# lens_controller2.net
KiCad netlist of a schematic drawn in EAGLE
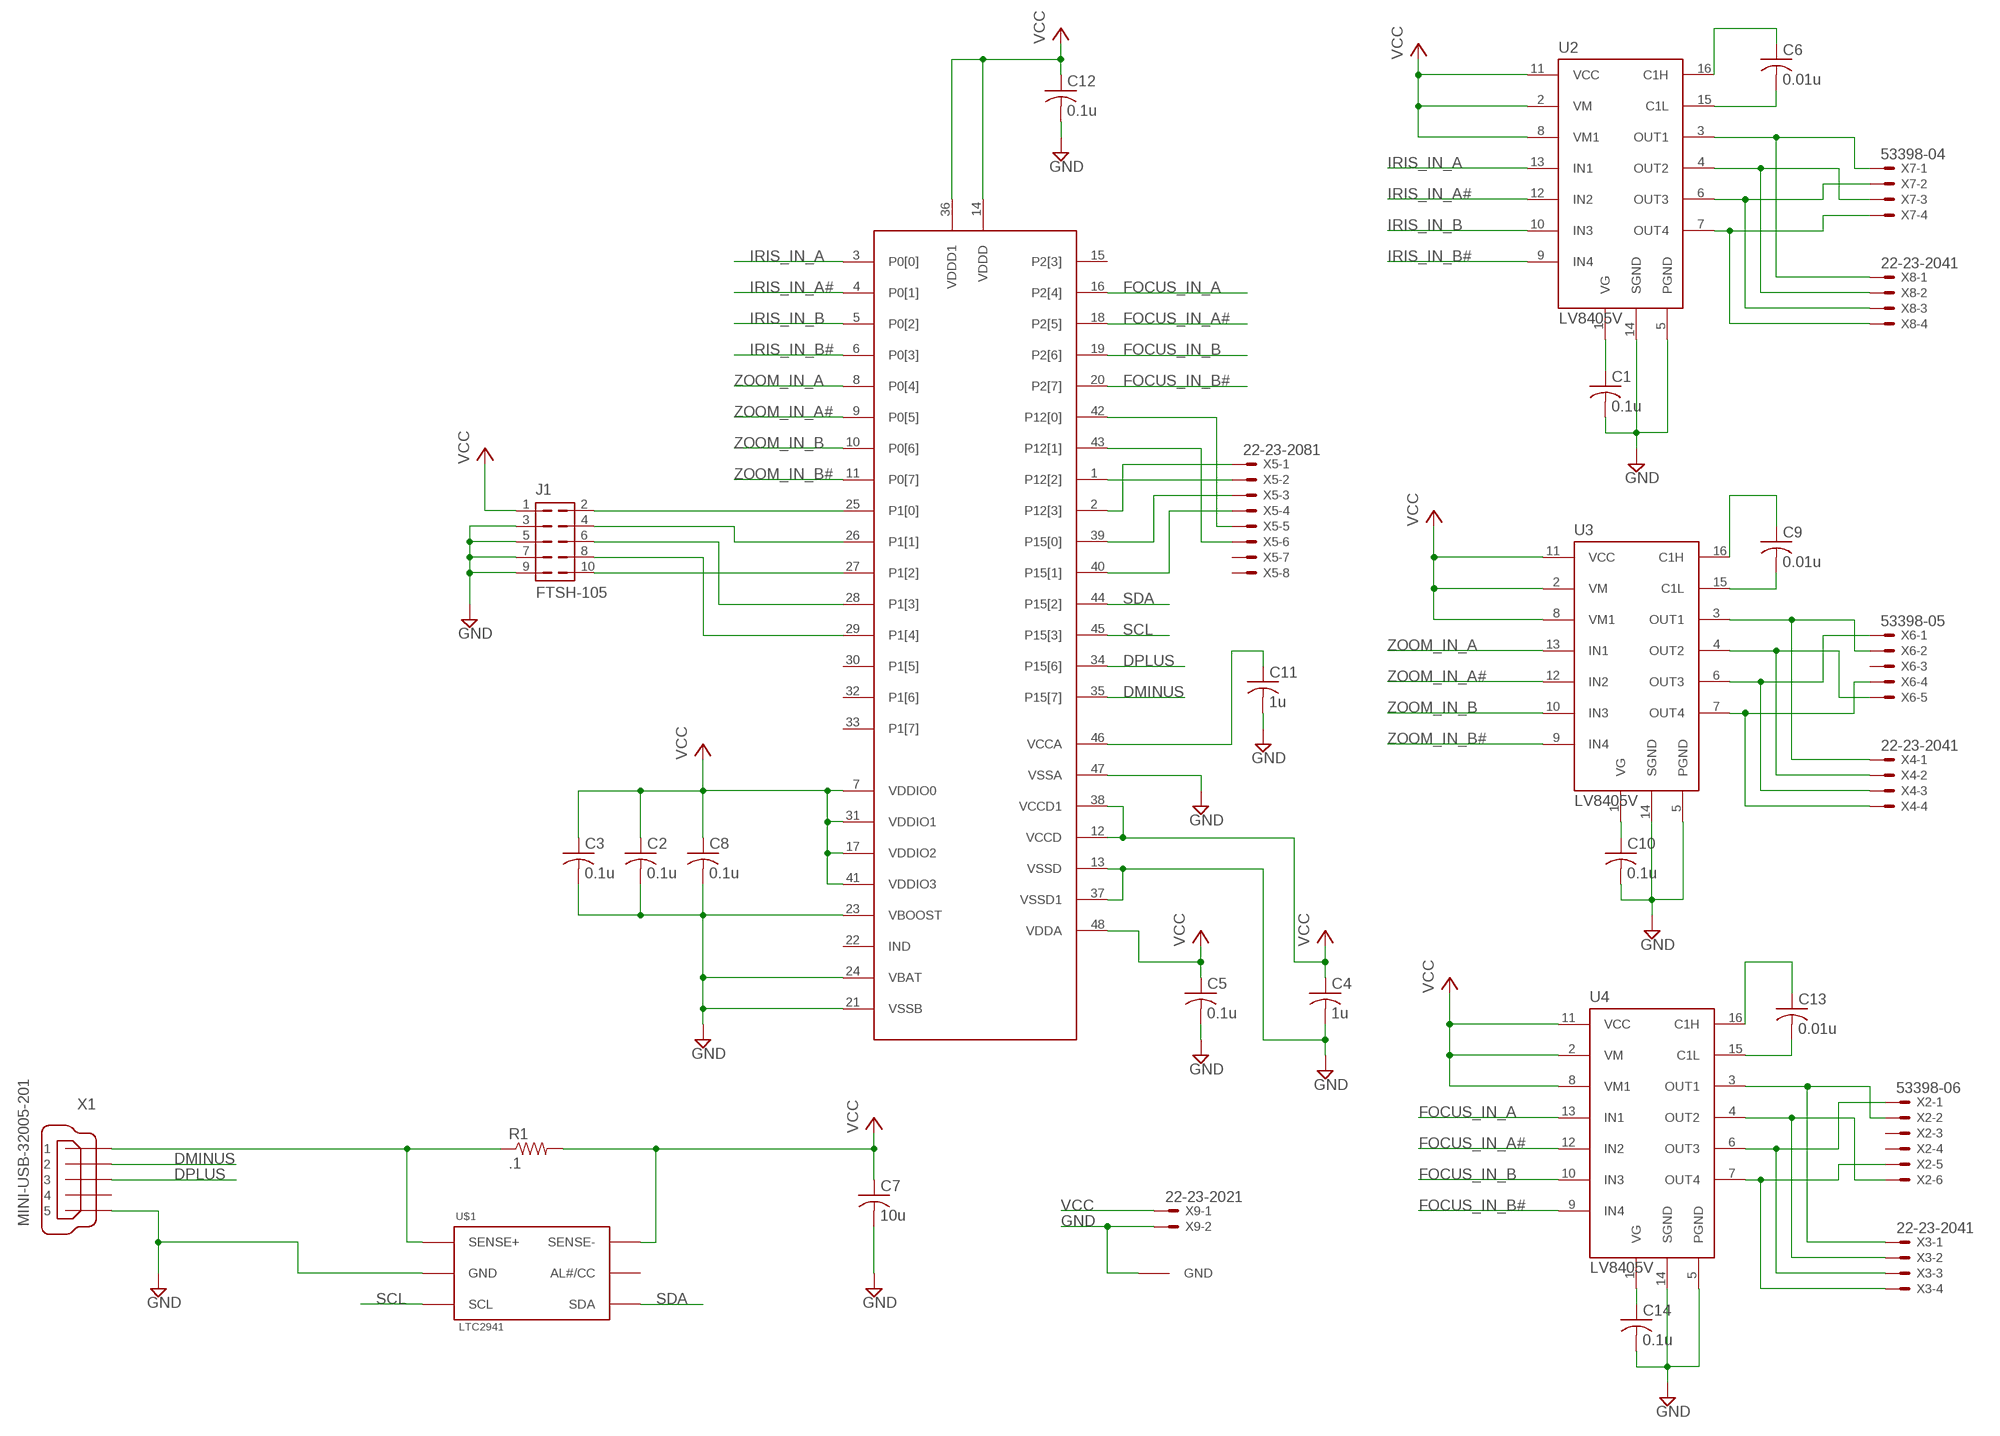
[diagram p0: schematic, sheet 1]

(export (version "E")
  (design (tool "Eeschema 10.0.6"))
  (components
    (comp (ref "C1")
      (value "0.1u")
      (footprint "eagle-import:C1206")
      (libsource (lib "eagle-import") (part "C-USC1206"))
    )
    (comp (ref "C2")
      (value "0.1u")
      (footprint "eagle-import:C1206")
      (libsource (lib "eagle-import") (part "C-USC1206"))
    )
    (comp (ref "C3")
      (value "0.1u")
      (footprint "eagle-import:C1206")
      (libsource (lib "eagle-import") (part "C-USC1206"))
    )
    (comp (ref "C4")
      (value "1u")
      (footprint "eagle-import:C1206")
      (libsource (lib "eagle-import") (part "C-USC1206"))
    )
    (comp (ref "C5")
      (value "0.1u")
      (footprint "eagle-import:C1206")
      (libsource (lib "eagle-import") (part "C-USC1206"))
    )
    (comp (ref "C6")
      (value "0.01u")
      (footprint "eagle-import:C1206")
      (libsource (lib "eagle-import") (part "C-USC1206"))
    )
    (comp (ref "C7")
      (value "10u")
      (footprint "eagle-import:C1206")
      (libsource (lib "eagle-import") (part "C-USC1206"))
    )
    (comp (ref "C8")
      (value "0.1u")
      (footprint "eagle-import:C1206")
      (libsource (lib "eagle-import") (part "C-USC1206"))
    )
    (comp (ref "C9")
      (value "0.01u")
      (footprint "eagle-import:C1206")
      (libsource (lib "eagle-import") (part "C-USC1206"))
    )
    (comp (ref "C10")
      (value "0.1u")
      (footprint "eagle-import:C1206")
      (libsource (lib "eagle-import") (part "C-USC1206"))
    )
    (comp (ref "C11")
      (value "1u")
      (footprint "eagle-import:C1206")
      (libsource (lib "eagle-import") (part "C-USC1206"))
    )
    (comp (ref "C12")
      (value "0.1u")
      (footprint "eagle-import:C1206")
      (libsource (lib "eagle-import") (part "C-USC1206"))
    )
    (comp (ref "C13")
      (value "0.01u")
      (footprint "eagle-import:C1206")
      (libsource (lib "eagle-import") (part "C-USC1206"))
    )
    (comp (ref "C14")
      (value "0.1u")
      (footprint "eagle-import:C1206")
      (libsource (lib "eagle-import") (part "C-USC1206"))
    )
    (comp (ref "J1")
      (value "FTSH-105")
      (footprint "eagle-import:FTSH-105-01-XXX-DV-K")
      (libsource (lib "eagle-import") (part "FTSH-105"))
    )
    (comp (ref "R1")
      (value ".1")
      (footprint "eagle-import:M1206")
      (libsource (lib "eagle-import") (part "R-US_M1206"))
    )
    (comp (ref "U$1")
      (value "LTC2941")
      (footprint "eagle-import:DFN6-2X3")
      (libsource (lib "eagle-import") (part "LTC2941"))
    )
    (comp (ref "U$5")
      (value "GND_LUG")
      (footprint "eagle-import:GND_PAD")
      (libsource (lib "eagle-import") (part "GND_LUG"))
    )
    (comp (ref "U1")
      (value "CY8C3246PVI")
      (footprint "eagle-import:SSOP48B")
      (libsource (lib "eagle-import") (part "CY8C3246PVI"))
    )
    (comp (ref "U2")
      (value "LV8405V")
      (footprint "eagle-import:SSOP16")
      (libsource (lib "eagle-import") (part "LV8405V"))
    )
    (comp (ref "U3")
      (value "LV8405V")
      (footprint "eagle-import:SSOP16")
      (libsource (lib "eagle-import") (part "LV8405V"))
    )
    (comp (ref "U4")
      (value "LV8405V")
      (footprint "eagle-import:SSOP16")
      (libsource (lib "eagle-import") (part "LV8405V"))
    )
    (comp (ref "X1")
      (value "MINI-USB-32005-201")
      (footprint "eagle-import:32005-201")
      (libsource (lib "eagle-import") (part "MINI-USB-32005-201"))
    )
    (comp (ref "X2")
      (value "53398-06")
      (footprint "eagle-import:53398-06")
      (libsource (lib "eagle-import") (part "53?-06398"))
    )
    (comp (ref "X3")
      (value "22-23-2041")
      (footprint "eagle-import:22-23-2041")
      (fields (field (name "MF") "MOLEX"))
      (libsource (lib "eagle-import") (part "22-23-2041"))
    )
    (comp (ref "X4")
      (value "22-23-2041")
      (footprint "eagle-import:22-23-2041")
      (fields (field (name "MF") "MOLEX"))
      (libsource (lib "eagle-import") (part "22-23-2041"))
    )
    (comp (ref "X5")
      (value "22-23-2081")
      (footprint "eagle-import:22-23-2081")
      (fields (field (name "MF") "MOLEX"))
      (libsource (lib "eagle-import") (part "22-23-2081"))
    )
    (comp (ref "X6")
      (value "53398-05")
      (footprint "eagle-import:53398-05")
      (libsource (lib "eagle-import") (part "53?-05398"))
    )
    (comp (ref "X7")
      (value "53398-04")
      (footprint "eagle-import:53398-04")
      (libsource (lib "eagle-import") (part "53?-04398"))
    )
    (comp (ref "X8")
      (value "22-23-2041")
      (footprint "eagle-import:22-23-2041")
      (fields (field (name "MF") "MOLEX"))
      (libsource (lib "eagle-import") (part "22-23-2041"))
    )
    (comp (ref "X9")
      (value "22-23-2021")
      (footprint "eagle-import:22-23-2021")
      (fields (field (name "MF") "MOLEX"))
      (libsource (lib "eagle-import") (part "22-23-2021"))
    )
  )
  (nets
    (net (code "1") (name "/DMINUS") (class "Default")
      (node (ref "U1") (pin "35") (pinfunction "P15[7]_35") (pintype "bidirectional"))
      (node (ref "X1") (pin "2") (pinfunction "2_2") (pintype "passive"))
    )
    (net (code "2") (name "/DPLUS") (class "Default")
      (node (ref "U1") (pin "34") (pinfunction "P15[6]_34") (pintype "bidirectional"))
      (node (ref "X1") (pin "3") (pinfunction "3_3") (pintype "passive"))
    )
    (net (code "3") (name "/FOCUS_IN_A") (class "Default")
      (node (ref "U1") (pin "16") (pinfunction "P2[4]_16") (pintype "bidirectional"))
      (node (ref "U4") (pin "13") (pinfunction "IN1_13") (pintype "bidirectional"))
    )
    (net (code "4") (name "/FOCUS_IN_A#") (class "Default")
      (node (ref "U1") (pin "18") (pinfunction "P2[5]_18") (pintype "bidirectional"))
      (node (ref "U4") (pin "12") (pinfunction "IN2_12") (pintype "bidirectional"))
    )
    (net (code "5") (name "/FOCUS_IN_B") (class "Default")
      (node (ref "U1") (pin "19") (pinfunction "P2[6]_19") (pintype "bidirectional"))
      (node (ref "U4") (pin "10") (pinfunction "IN3_10") (pintype "bidirectional"))
    )
    (net (code "6") (name "/FOCUS_IN_B#") (class "Default")
      (node (ref "U1") (pin "20") (pinfunction "P2[7]_20") (pintype "bidirectional"))
      (node (ref "U4") (pin "9") (pinfunction "IN4_9") (pintype "bidirectional"))
    )
    (net (code "7") (name "/IRIS_IN_A") (class "Default")
      (node (ref "U1") (pin "3") (pinfunction "P0[0]_3") (pintype "bidirectional"))
      (node (ref "U2") (pin "13") (pinfunction "IN1_13") (pintype "bidirectional"))
    )
    (net (code "8") (name "/IRIS_IN_A#") (class "Default")
      (node (ref "U1") (pin "4") (pinfunction "P0[1]_4") (pintype "bidirectional"))
      (node (ref "U2") (pin "12") (pinfunction "IN2_12") (pintype "bidirectional"))
    )
    (net (code "9") (name "/IRIS_IN_B") (class "Default")
      (node (ref "U1") (pin "5") (pinfunction "P0[2]_5") (pintype "bidirectional"))
      (node (ref "U2") (pin "10") (pinfunction "IN3_10") (pintype "bidirectional"))
    )
    (net (code "10") (name "/IRIS_IN_B#") (class "Default")
      (node (ref "U1") (pin "6") (pinfunction "P0[3]_6") (pintype "bidirectional"))
      (node (ref "U2") (pin "9") (pinfunction "IN4_9") (pintype "bidirectional"))
    )
    (net (code "11") (name "/SCL") (class "Default")
      (node (ref "U$1") (pin "3") (pinfunction "SCL_3") (pintype "bidirectional"))
      (node (ref "U1") (pin "45") (pinfunction "P15[3]_45") (pintype "bidirectional"))
    )
    (net (code "12") (name "/SDA") (class "Default")
      (node (ref "U$1") (pin "4") (pinfunction "SDA_4") (pintype "bidirectional"))
      (node (ref "U1") (pin "44") (pinfunction "P15[2]_44") (pintype "bidirectional"))
    )
    (net (code "13") (name "/ZOOM_IN_A") (class "Default")
      (node (ref "U1") (pin "8") (pinfunction "P0[4]_8") (pintype "bidirectional"))
      (node (ref "U3") (pin "13") (pinfunction "IN1_13") (pintype "bidirectional"))
    )
    (net (code "14") (name "/ZOOM_IN_A#") (class "Default")
      (node (ref "U1") (pin "9") (pinfunction "P0[5]_9") (pintype "bidirectional"))
      (node (ref "U3") (pin "12") (pinfunction "IN2_12") (pintype "bidirectional"))
    )
    (net (code "15") (name "/ZOOM_IN_B") (class "Default")
      (node (ref "U1") (pin "10") (pinfunction "P0[6]_10") (pintype "bidirectional"))
      (node (ref "U3") (pin "10") (pinfunction "IN3_10") (pintype "bidirectional"))
    )
    (net (code "16") (name "/ZOOM_IN_B#") (class "Default")
      (node (ref "U1") (pin "11") (pinfunction "P0[7]_11") (pintype "bidirectional"))
      (node (ref "U3") (pin "9") (pinfunction "IN4_9") (pintype "bidirectional"))
    )
    (net (code "17") (name "GND") (class "Default")
      (node (ref "C1") (pin "2") (pinfunction "2_2") (pintype "passive"))
      (node (ref "C10") (pin "2") (pinfunction "2_2") (pintype "passive"))
      (node (ref "C11") (pin "2") (pinfunction "2_2") (pintype "passive"))
      (node (ref "C12") (pin "2") (pinfunction "2_2") (pintype "passive"))
      (node (ref "C14") (pin "2") (pinfunction "2_2") (pintype "passive"))
      (node (ref "C2") (pin "2") (pinfunction "2_2") (pintype "passive"))
      (node (ref "C3") (pin "2") (pinfunction "2_2") (pintype "passive"))
      (node (ref "C4") (pin "2") (pinfunction "2_2") (pintype "passive"))
      (node (ref "C5") (pin "2") (pinfunction "2_2") (pintype "passive"))
      (node (ref "C7") (pin "2") (pinfunction "2_2") (pintype "passive"))
      (node (ref "C8") (pin "2") (pinfunction "2_2") (pintype "passive"))
      (node (ref "J1") (pin "3") (pinfunction "3_3") (pintype "passive"))
      (node (ref "J1") (pin "5") (pinfunction "5_5") (pintype "passive"))
      (node (ref "J1") (pin "7") (pinfunction "7_7") (pintype "passive"))
      (node (ref "J1") (pin "9") (pinfunction "9_9") (pintype "passive"))
      (node (ref "U$1") (pin "2") (pinfunction "GND_2") (pintype "bidirectional"))
      (node (ref "U$5") (pin "P$1") (pinfunction "GND_P$1") (pintype "bidirectional"))
      (node (ref "U1") (pin "13") (pinfunction "VSSD_13") (pintype "bidirectional"))
      (node (ref "U1") (pin "21") (pinfunction "VSSB_21") (pintype "bidirectional"))
      (node (ref "U1") (pin "23") (pinfunction "VBOOST_23") (pintype "bidirectional"))
      (node (ref "U1") (pin "24") (pinfunction "VBAT_24") (pintype "bidirectional"))
      (node (ref "U1") (pin "37") (pinfunction "VSSD1_37") (pintype "bidirectional"))
      (node (ref "U1") (pin "47") (pinfunction "VSSA_47") (pintype "bidirectional"))
      (node (ref "U2") (pin "14") (pinfunction "SGND_14") (pintype "bidirectional"))
      (node (ref "U2") (pin "5") (pinfunction "PGND_5") (pintype "bidirectional"))
      (node (ref "U3") (pin "14") (pinfunction "SGND_14") (pintype "bidirectional"))
      (node (ref "U3") (pin "5") (pinfunction "PGND_5") (pintype "bidirectional"))
      (node (ref "U4") (pin "14") (pinfunction "SGND_14") (pintype "bidirectional"))
      (node (ref "U4") (pin "5") (pinfunction "PGND_5") (pintype "bidirectional"))
      (node (ref "X1") (pin "5") (pinfunction "5_5") (pintype "passive"))
      (node (ref "X9") (pin "2") (pinfunction "S_2") (pintype "passive"))
    )
    (net (code "18") (name "Net-(U$1-SENSE+)") (class "Default")
      (node (ref "R1") (pin "1") (pinfunction "1_1") (pintype "passive"))
      (node (ref "U$1") (pin "1") (pinfunction "SENSE+_1") (pintype "bidirectional"))
      (node (ref "X1") (pin "1") (pinfunction "1_1") (pintype "passive"))
    )
    (net (code "19") (name "Net-(U1-P1[0])") (class "Default")
      (node (ref "J1") (pin "2") (pinfunction "2_2") (pintype "passive"))
      (node (ref "U1") (pin "25") (pinfunction "P1[0]_25") (pintype "bidirectional"))
    )
    (net (code "20") (name "Net-(U1-P1[1])") (class "Default")
      (node (ref "J1") (pin "4") (pinfunction "4_4") (pintype "passive"))
      (node (ref "U1") (pin "26") (pinfunction "P1[1]_26") (pintype "bidirectional"))
    )
    (net (code "21") (name "Net-(U1-P1[2])") (class "Default")
      (node (ref "J1") (pin "10") (pinfunction "10_10") (pintype "passive"))
      (node (ref "U1") (pin "27") (pinfunction "P1[2]_27") (pintype "bidirectional"))
    )
    (net (code "22") (name "Net-(U1-P1[3])") (class "Default")
      (node (ref "J1") (pin "6") (pinfunction "6_6") (pintype "passive"))
      (node (ref "U1") (pin "28") (pinfunction "P1[3]_28") (pintype "bidirectional"))
    )
    (net (code "23") (name "Net-(U1-P1[4])") (class "Default")
      (node (ref "J1") (pin "8") (pinfunction "8_8") (pintype "passive"))
      (node (ref "U1") (pin "29") (pinfunction "P1[4]_29") (pintype "bidirectional"))
    )
    (net (code "24") (name "Net-(U1-P12[0])") (class "Default")
      (node (ref "U1") (pin "42") (pinfunction "P12[0]_42") (pintype "bidirectional"))
      (node (ref "X5") (pin "5") (pinfunction "S_5") (pintype "passive"))
    )
    (net (code "25") (name "Net-(U1-P12[1])") (class "Default")
      (node (ref "U1") (pin "43") (pinfunction "P12[1]_43") (pintype "bidirectional"))
      (node (ref "X5") (pin "6") (pinfunction "S_6") (pintype "passive"))
    )
    (net (code "26") (name "Net-(U1-P12[2])") (class "Default")
      (node (ref "U1") (pin "1") (pinfunction "P12[2]_1") (pintype "bidirectional"))
      (node (ref "X5") (pin "2") (pinfunction "S_2") (pintype "passive"))
    )
    (net (code "27") (name "Net-(U1-P12[3])") (class "Default")
      (node (ref "U1") (pin "2") (pinfunction "P12[3]_2") (pintype "bidirectional"))
      (node (ref "X5") (pin "1") (pinfunction "S_1") (pintype "passive"))
    )
    (net (code "28") (name "Net-(U1-P15[0])") (class "Default")
      (node (ref "U1") (pin "39") (pinfunction "P15[0]_39") (pintype "bidirectional"))
      (node (ref "X5") (pin "3") (pinfunction "S_3") (pintype "passive"))
    )
    (net (code "29") (name "Net-(U1-P15[1])") (class "Default")
      (node (ref "U1") (pin "40") (pinfunction "P15[1]_40") (pintype "bidirectional"))
      (node (ref "X5") (pin "4") (pinfunction "S_4") (pintype "passive"))
    )
    (net (code "30") (name "Net-(U1-VCCA)") (class "Default")
      (node (ref "C11") (pin "1") (pinfunction "1_1") (pintype "passive"))
      (node (ref "U1") (pin "46") (pinfunction "VCCA_46") (pintype "bidirectional"))
    )
    (net (code "31") (name "Net-(U2-C1H)") (class "Default")
      (node (ref "C6") (pin "1") (pinfunction "1_1") (pintype "passive"))
      (node (ref "U2") (pin "16") (pinfunction "C1H_16") (pintype "bidirectional"))
    )
    (net (code "32") (name "Net-(U2-C1L)") (class "Default")
      (node (ref "C6") (pin "2") (pinfunction "2_2") (pintype "passive"))
      (node (ref "U2") (pin "15") (pinfunction "C1L_15") (pintype "bidirectional"))
    )
    (net (code "33") (name "Net-(U2-OUT1)") (class "Default")
      (node (ref "U2") (pin "3") (pinfunction "OUT1_3") (pintype "bidirectional"))
      (node (ref "X7") (pin "1") (pinfunction "S_1") (pintype "passive"))
      (node (ref "X8") (pin "1") (pinfunction "S_1") (pintype "passive"))
    )
    (net (code "34") (name "Net-(U2-OUT2)") (class "Default")
      (node (ref "U2") (pin "4") (pinfunction "OUT2_4") (pintype "bidirectional"))
      (node (ref "X7") (pin "3") (pinfunction "S_3") (pintype "passive"))
      (node (ref "X8") (pin "2") (pinfunction "S_2") (pintype "passive"))
    )
    (net (code "35") (name "Net-(U2-OUT3)") (class "Default")
      (node (ref "U2") (pin "6") (pinfunction "OUT3_6") (pintype "bidirectional"))
      (node (ref "X7") (pin "2") (pinfunction "S_2") (pintype "passive"))
      (node (ref "X8") (pin "3") (pinfunction "S_3") (pintype "passive"))
    )
    (net (code "36") (name "Net-(U2-OUT4)") (class "Default")
      (node (ref "U2") (pin "7") (pinfunction "OUT4_7") (pintype "bidirectional"))
      (node (ref "X7") (pin "4") (pinfunction "S_4") (pintype "passive"))
      (node (ref "X8") (pin "4") (pinfunction "S_4") (pintype "passive"))
    )
    (net (code "37") (name "Net-(U2-VG)") (class "Default")
      (node (ref "C1") (pin "1") (pinfunction "1_1") (pintype "passive"))
      (node (ref "U2") (pin "1") (pinfunction "VG_1") (pintype "bidirectional"))
    )
    (net (code "38") (name "Net-(U3-C1H)") (class "Default")
      (node (ref "C9") (pin "1") (pinfunction "1_1") (pintype "passive"))
      (node (ref "U3") (pin "16") (pinfunction "C1H_16") (pintype "bidirectional"))
    )
    (net (code "39") (name "Net-(U3-C1L)") (class "Default")
      (node (ref "C9") (pin "2") (pinfunction "2_2") (pintype "passive"))
      (node (ref "U3") (pin "15") (pinfunction "C1L_15") (pintype "bidirectional"))
    )
    (net (code "40") (name "Net-(U3-OUT1)") (class "Default")
      (node (ref "U3") (pin "3") (pinfunction "OUT1_3") (pintype "bidirectional"))
      (node (ref "X4") (pin "1") (pinfunction "S_1") (pintype "passive"))
      (node (ref "X6") (pin "2") (pinfunction "S_2") (pintype "passive"))
    )
    (net (code "41") (name "Net-(U3-OUT2)") (class "Default")
      (node (ref "U3") (pin "4") (pinfunction "OUT2_4") (pintype "bidirectional"))
      (node (ref "X4") (pin "2") (pinfunction "S_2") (pintype "passive"))
      (node (ref "X6") (pin "5") (pinfunction "S_5") (pintype "passive"))
    )
    (net (code "42") (name "Net-(U3-OUT3)") (class "Default")
      (node (ref "U3") (pin "6") (pinfunction "OUT3_6") (pintype "bidirectional"))
      (node (ref "X4") (pin "3") (pinfunction "S_3") (pintype "passive"))
      (node (ref "X6") (pin "1") (pinfunction "S_1") (pintype "passive"))
    )
    (net (code "43") (name "Net-(U3-OUT4)") (class "Default")
      (node (ref "U3") (pin "7") (pinfunction "OUT4_7") (pintype "bidirectional"))
      (node (ref "X4") (pin "4") (pinfunction "S_4") (pintype "passive"))
      (node (ref "X6") (pin "4") (pinfunction "S_4") (pintype "passive"))
    )
    (net (code "44") (name "Net-(U3-VG)") (class "Default")
      (node (ref "C10") (pin "1") (pinfunction "1_1") (pintype "passive"))
      (node (ref "U3") (pin "1") (pinfunction "VG_1") (pintype "bidirectional"))
    )
    (net (code "45") (name "Net-(U4-C1H)") (class "Default")
      (node (ref "C13") (pin "1") (pinfunction "1_1") (pintype "passive"))
      (node (ref "U4") (pin "16") (pinfunction "C1H_16") (pintype "bidirectional"))
    )
    (net (code "46") (name "Net-(U4-C1L)") (class "Default")
      (node (ref "C13") (pin "2") (pinfunction "2_2") (pintype "passive"))
      (node (ref "U4") (pin "15") (pinfunction "C1L_15") (pintype "bidirectional"))
    )
    (net (code "47") (name "Net-(U4-OUT1)") (class "Default")
      (node (ref "U4") (pin "3") (pinfunction "OUT1_3") (pintype "bidirectional"))
      (node (ref "X2") (pin "2") (pinfunction "S_2") (pintype "passive"))
      (node (ref "X3") (pin "1") (pinfunction "S_1") (pintype "passive"))
    )
    (net (code "48") (name "Net-(U4-OUT2)") (class "Default")
      (node (ref "U4") (pin "4") (pinfunction "OUT2_4") (pintype "bidirectional"))
      (node (ref "X2") (pin "6") (pinfunction "S_6") (pintype "passive"))
      (node (ref "X3") (pin "2") (pinfunction "S_2") (pintype "passive"))
    )
    (net (code "49") (name "Net-(U4-OUT3)") (class "Default")
      (node (ref "U4") (pin "6") (pinfunction "OUT3_6") (pintype "bidirectional"))
      (node (ref "X2") (pin "1") (pinfunction "S_1") (pintype "passive"))
      (node (ref "X3") (pin "3") (pinfunction "S_3") (pintype "passive"))
    )
    (net (code "50") (name "Net-(U4-OUT4)") (class "Default")
      (node (ref "U4") (pin "7") (pinfunction "OUT4_7") (pintype "bidirectional"))
      (node (ref "X2") (pin "5") (pinfunction "S_5") (pintype "passive"))
      (node (ref "X3") (pin "4") (pinfunction "S_4") (pintype "passive"))
    )
    (net (code "51") (name "Net-(U4-VG)") (class "Default")
      (node (ref "C14") (pin "1") (pinfunction "1_1") (pintype "passive"))
      (node (ref "U4") (pin "1") (pinfunction "VG_1") (pintype "bidirectional"))
    )
    (net (code "52") (name "VCC") (class "Default")
      (node (ref "C12") (pin "1") (pinfunction "1_1") (pintype "passive"))
      (node (ref "C2") (pin "1") (pinfunction "1_1") (pintype "passive"))
      (node (ref "C3") (pin "1") (pinfunction "1_1") (pintype "passive"))
      (node (ref "C4") (pin "1") (pinfunction "1_1") (pintype "passive"))
      (node (ref "C5") (pin "1") (pinfunction "1_1") (pintype "passive"))
      (node (ref "C7") (pin "1") (pinfunction "1_1") (pintype "passive"))
      (node (ref "C8") (pin "1") (pinfunction "1_1") (pintype "passive"))
      (node (ref "J1") (pin "1") (pinfunction "1_1") (pintype "passive"))
      (node (ref "R1") (pin "2") (pinfunction "2_2") (pintype "passive"))
      (node (ref "U$1") (pin "6") (pinfunction "SENSE-_6") (pintype "bidirectional"))
      (node (ref "U1") (pin "12") (pinfunction "VCCD_12") (pintype "bidirectional"))
      (node (ref "U1") (pin "14") (pinfunction "VDDD_14") (pintype "bidirectional"))
      (node (ref "U1") (pin "17") (pinfunction "VDDIO2_17") (pintype "bidirectional"))
      (node (ref "U1") (pin "31") (pinfunction "VDDIO1_31") (pintype "bidirectional"))
      (node (ref "U1") (pin "36") (pinfunction "VDDD1_36") (pintype "bidirectional"))
      (node (ref "U1") (pin "38") (pinfunction "VCCD1_38") (pintype "bidirectional"))
      (node (ref "U1") (pin "41") (pinfunction "VDDIO3_41") (pintype "bidirectional"))
      (node (ref "U1") (pin "48") (pinfunction "VDDA_48") (pintype "bidirectional"))
      (node (ref "U1") (pin "7") (pinfunction "VDDIO0_7") (pintype "bidirectional"))
      (node (ref "U2") (pin "11") (pinfunction "VCC_11") (pintype "bidirectional"))
      (node (ref "U2") (pin "2") (pinfunction "VM_2") (pintype "bidirectional"))
      (node (ref "U2") (pin "8") (pinfunction "VM1_8") (pintype "bidirectional"))
      (node (ref "U3") (pin "11") (pinfunction "VCC_11") (pintype "bidirectional"))
      (node (ref "U3") (pin "2") (pinfunction "VM_2") (pintype "bidirectional"))
      (node (ref "U3") (pin "8") (pinfunction "VM1_8") (pintype "bidirectional"))
      (node (ref "U4") (pin "11") (pinfunction "VCC_11") (pintype "bidirectional"))
      (node (ref "U4") (pin "2") (pinfunction "VM_2") (pintype "bidirectional"))
      (node (ref "U4") (pin "8") (pinfunction "VM1_8") (pintype "bidirectional"))
      (node (ref "X9") (pin "1") (pinfunction "S_1") (pintype "passive"))
    )
    (net (code "53") (name "unconnected-(U$1-AL#{slash}CC-Pad5)") (class "Default")
      (node (ref "U$1") (pin "5") (pinfunction "AL#/CC_5") (pintype "bidirectional"))
    )
    (net (code "54") (name "unconnected-(U1-IND-Pad22)") (class "Default")
      (node (ref "U1") (pin "22") (pinfunction "IND_22") (pintype "bidirectional"))
    )
    (net (code "55") (name "unconnected-(U1-P1[5]-Pad30)") (class "Default")
      (node (ref "U1") (pin "30") (pinfunction "P1[5]_30") (pintype "bidirectional"))
    )
    (net (code "56") (name "unconnected-(U1-P1[6]-Pad32)") (class "Default")
      (node (ref "U1") (pin "32") (pinfunction "P1[6]_32") (pintype "bidirectional"))
    )
    (net (code "57") (name "unconnected-(U1-P1[7]-Pad33)") (class "Default")
      (node (ref "U1") (pin "33") (pinfunction "P1[7]_33") (pintype "bidirectional"))
    )
    (net (code "58") (name "unconnected-(U1-P2[3]-Pad15)") (class "Default")
      (node (ref "U1") (pin "15") (pinfunction "P2[3]_15") (pintype "bidirectional"))
    )
    (net (code "59") (name "unconnected-(X1-Pad4)") (class "Default")
      (node (ref "X1") (pin "4") (pinfunction "4_4") (pintype "passive"))
    )
    (net (code "60") (name "unconnected-(X2C-S-Pad3)") (class "Default")
      (node (ref "X2") (pin "3") (pinfunction "S_3") (pintype "passive"))
    )
    (net (code "61") (name "unconnected-(X2D-S-Pad4)") (class "Default")
      (node (ref "X2") (pin "4") (pinfunction "S_4") (pintype "passive"))
    )
    (net (code "62") (name "unconnected-(X5G-S-Pad7)") (class "Default")
      (node (ref "X5") (pin "7") (pinfunction "S_7") (pintype "passive"))
    )
    (net (code "63") (name "unconnected-(X5H-S-Pad8)") (class "Default")
      (node (ref "X5") (pin "8") (pinfunction "S_8") (pintype "passive"))
    )
    (net (code "64") (name "unconnected-(X6C-S-Pad3)") (class "Default")
      (node (ref "X6") (pin "3") (pinfunction "S_3") (pintype "passive"))
    )
  )
)
